# Tiefenentladeschutz_2.net
KiCad netlist of a schematic drawn in EAGLE
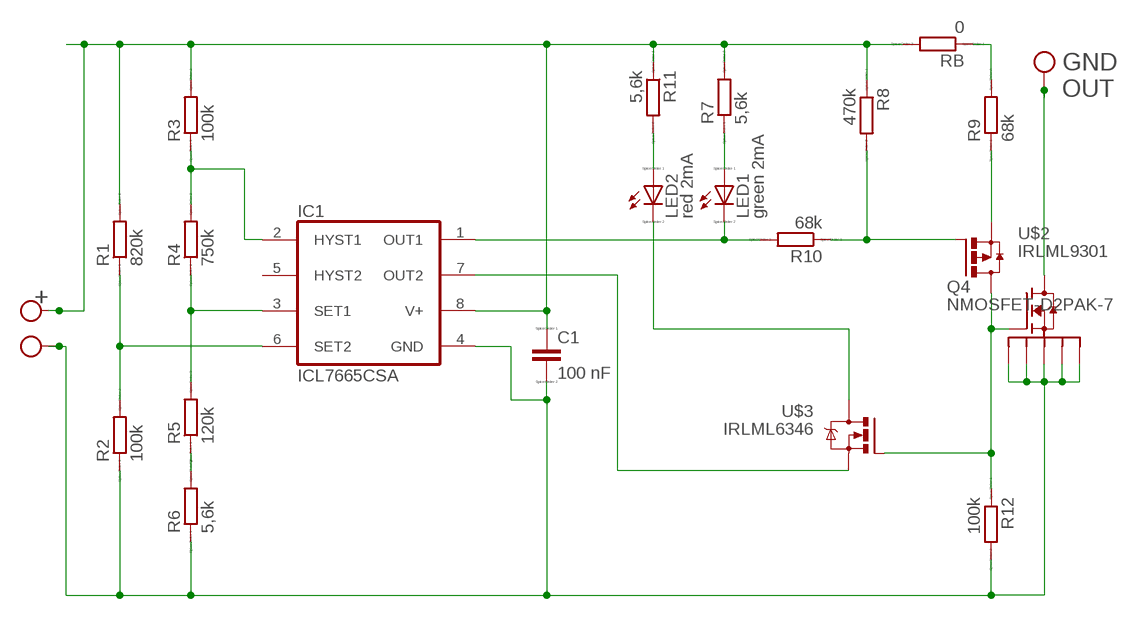
[diagram p0: schematic, sheet 1]

(export (version "E")
  (design (tool "Eeschema 10.0.6"))
  (components
    (comp (ref "C1")
      (value "100 nF")
      (footprint "eagle-import:C1206")
      (libsource (lib "eagle-import") (part "CC1206"))
    )
    (comp (ref "IC1")
      (value "ICL7665CSA")
      (footprint "eagle-import:SO08")
      (fields (field (name "MPN") "ICL7665CSA+"))
      (libsource (lib "eagle-import") (part "ICL7665CSA"))
    )
    (comp (ref "LED1")
      (value "green 2mA")
      (footprint "eagle-import:LED_SML0603")
      (libsource (lib "eagle-import") (part "LED_ESML0603"))
    )
    (comp (ref "LED2")
      (value "red 2mA")
      (footprint "eagle-import:LED_SML0603")
      (libsource (lib "eagle-import") (part "LED_ESML0603"))
    )
    (comp (ref "Q4")
      (value "NMOSFET-D2PAK-7")
      (footprint "eagle-import:H2PAK-6")
      (libsource (lib "eagle-import") (part "NMOSFET-D2PAK-7"))
    )
    (comp (ref "R1")
      (value "820k")
      (footprint "eagle-import:R1206")
      (libsource (lib "eagle-import") (part "RR1206"))
    )
    (comp (ref "R2")
      (value "100k")
      (footprint "eagle-import:R1206")
      (libsource (lib "eagle-import") (part "RR1206"))
    )
    (comp (ref "R3")
      (value "100k")
      (footprint "eagle-import:R1206")
      (libsource (lib "eagle-import") (part "RR1206"))
    )
    (comp (ref "R4")
      (value "750k")
      (footprint "eagle-import:R1206")
      (libsource (lib "eagle-import") (part "RR1206"))
    )
    (comp (ref "R5")
      (value "120k")
      (footprint "eagle-import:R1206")
      (libsource (lib "eagle-import") (part "RR1206"))
    )
    (comp (ref "R6")
      (value "5,6k")
      (footprint "eagle-import:R1206")
      (libsource (lib "eagle-import") (part "RR1206"))
    )
    (comp (ref "R7")
      (value "5,6k")
      (footprint "eagle-import:R1206")
      (libsource (lib "eagle-import") (part "RR1206"))
    )
    (comp (ref "R8")
      (value "470k")
      (footprint "eagle-import:R1206")
      (libsource (lib "eagle-import") (part "RR1206"))
    )
    (comp (ref "R9")
      (value "68k")
      (footprint "eagle-import:R1206")
      (libsource (lib "eagle-import") (part "RR1206"))
    )
    (comp (ref "R10")
      (value "68k")
      (footprint "eagle-import:R1206")
      (libsource (lib "eagle-import") (part "RR1206"))
    )
    (comp (ref "R11")
      (value "5,6k")
      (footprint "eagle-import:R1206")
      (libsource (lib "eagle-import") (part "RR1206"))
    )
    (comp (ref "R12")
      (value "100k")
      (footprint "eagle-import:R1206")
      (libsource (lib "eagle-import") (part "RR1206"))
    )
    (comp (ref "RB")
      (value "0")
      (footprint "eagle-import:R1206")
      (libsource (lib "eagle-import") (part "RR1206"))
    )
    (comp (ref "U$2")
      (value "IRLML9301")
      (footprint "eagle-import:SOT-23")
      (libsource (lib "eagle-import") (part "IRLML9301"))
    )
    (comp (ref "U$3")
      (value "IRLML6346")
      (footprint "eagle-import:SOT-23")
      (libsource (lib "eagle-import") (part "IRLML6346"))
    )
    (comp (ref "U$4")
      (value "PINBIG")
      (footprint "eagle-import:PIN")
      (libsource (lib "eagle-import") (part "PINBIG"))
    )
    (comp (ref "U$6")
      (value "PIN1.27")
      (footprint "eagle-import:PIN-1.27")
      (libsource (lib "eagle-import") (part "PIN1.27"))
    )
    (comp (ref "U$7")
      (value "PIN1.27")
      (footprint "eagle-import:PIN-1.27")
      (libsource (lib "eagle-import") (part "PIN1.27"))
    )
  )
  (nets
    (net (code "1") (name "Net-(IC1-GND)") (class "Default")
      (node (ref "C1") (pin "2") (pinfunction "2_2") (pintype "passive"))
      (node (ref "IC1") (pin "4") (pinfunction "GND_4") (pintype "power_in"))
      (node (ref "Q4") (pin "S1") (pinfunction "S1_S1") (pintype "passive"))
      (node (ref "Q4") (pin "S2") (pinfunction "S2_S2") (pintype "passive"))
      (node (ref "Q4") (pin "S3") (pinfunction "S3_S3") (pintype "passive"))
      (node (ref "Q4") (pin "S4") (pinfunction "S4_S4") (pintype "passive"))
      (node (ref "Q4") (pin "S5") (pinfunction "S5_S5") (pintype "passive"))
      (node (ref "R12") (pin "2") (pinfunction "2_2") (pintype "passive"))
      (node (ref "R2") (pin "1") (pinfunction "1_1") (pintype "passive"))
      (node (ref "R6") (pin "1") (pinfunction "1_1") (pintype "passive"))
      (node (ref "U$6") (pin "P$1") (pinfunction "P$1_P$1") (pintype "bidirectional"))
    )
    (net (code "2") (name "Net-(IC1-HYST1)") (class "Default")
      (node (ref "IC1") (pin "2") (pinfunction "HYST1_2") (pintype "input"))
      (node (ref "R3") (pin "1") (pinfunction "1_1") (pintype "passive"))
      (node (ref "R4") (pin "2") (pinfunction "2_2") (pintype "passive"))
    )
    (net (code "3") (name "Net-(IC1-OUT1)") (class "Default")
      (node (ref "IC1") (pin "1") (pinfunction "OUT1_1") (pintype "output"))
      (node (ref "LED1") (pin "C") (pinfunction "C_C") (pintype "passive"))
      (node (ref "R10") (pin "2") (pinfunction "2_2") (pintype "passive"))
    )
    (net (code "4") (name "Net-(IC1-OUT2)") (class "Default")
      (node (ref "IC1") (pin "7") (pinfunction "OUT2_7") (pintype "output"))
      (node (ref "U$3") (pin "2") (pinfunction "S_2") (pintype "passive"))
    )
    (net (code "5") (name "Net-(IC1-SET1)") (class "Default")
      (node (ref "IC1") (pin "3") (pinfunction "SET1_3") (pintype "input"))
      (node (ref "R4") (pin "1") (pinfunction "1_1") (pintype "passive"))
      (node (ref "R5") (pin "2") (pinfunction "2_2") (pintype "passive"))
    )
    (net (code "6") (name "Net-(IC1-SET2)") (class "Default")
      (node (ref "IC1") (pin "6") (pinfunction "SET2_6") (pintype "input"))
      (node (ref "R1") (pin "1") (pinfunction "1_1") (pintype "passive"))
      (node (ref "R2") (pin "2") (pinfunction "2_2") (pintype "passive"))
    )
    (net (code "7") (name "Net-(IC1-V+)") (class "Default")
      (node (ref "C1") (pin "1") (pinfunction "1_1") (pintype "passive"))
      (node (ref "IC1") (pin "8") (pinfunction "V+_8") (pintype "power_in"))
      (node (ref "R1") (pin "2") (pinfunction "2_2") (pintype "passive"))
      (node (ref "R11") (pin "1") (pinfunction "1_1") (pintype "passive"))
      (node (ref "R3") (pin "2") (pinfunction "2_2") (pintype "passive"))
      (node (ref "R7") (pin "2") (pinfunction "2_2") (pintype "passive"))
      (node (ref "R8") (pin "1") (pinfunction "1_1") (pintype "passive"))
      (node (ref "RB") (pin "2") (pinfunction "2_2") (pintype "passive"))
      (node (ref "U$4") (pin "P$1") (pinfunction "P$1_P$1") (pintype "bidirectional"))
    )
    (net (code "8") (name "Net-(LED1-PadA)") (class "Default")
      (node (ref "LED1") (pin "A") (pinfunction "A_A") (pintype "passive"))
      (node (ref "R7") (pin "1") (pinfunction "1_1") (pintype "passive"))
    )
    (net (code "9") (name "Net-(LED2-PadA)") (class "Default")
      (node (ref "LED2") (pin "A") (pinfunction "A_A") (pintype "passive"))
      (node (ref "R11") (pin "2") (pinfunction "2_2") (pintype "passive"))
    )
    (net (code "10") (name "Net-(Q4-PadD)") (class "Default")
      (node (ref "Q4") (pin "D") (pinfunction "D_D") (pintype "passive"))
      (node (ref "U$7") (pin "P$1") (pinfunction "P$1_P$1") (pintype "bidirectional"))
    )
    (net (code "11") (name "Net-(R5-Pad1)") (class "Default")
      (node (ref "R5") (pin "1") (pinfunction "1_1") (pintype "passive"))
      (node (ref "R6") (pin "2") (pinfunction "2_2") (pintype "passive"))
    )
    (net (code "12") (name "Net-(R9-Pad2)") (class "Default")
      (node (ref "R9") (pin "2") (pinfunction "2_2") (pintype "passive"))
      (node (ref "RB") (pin "1") (pinfunction "1_1") (pintype "passive"))
    )
    (net (code "13") (name "Net-(U$2-D)") (class "Default")
      (node (ref "Q4") (pin "G") (pinfunction "G_G") (pintype "passive"))
      (node (ref "R12") (pin "1") (pinfunction "1_1") (pintype "passive"))
      (node (ref "U$2") (pin "1") (pinfunction "D_1") (pintype "passive"))
      (node (ref "U$3") (pin "3") (pinfunction "G_3") (pintype "passive"))
    )
    (net (code "14") (name "Net-(U$2-G)") (class "Default")
      (node (ref "R10") (pin "1") (pinfunction "1_1") (pintype "passive"))
      (node (ref "R8") (pin "2") (pinfunction "2_2") (pintype "passive"))
      (node (ref "U$2") (pin "3") (pinfunction "G_3") (pintype "passive"))
    )
    (net (code "15") (name "Net-(U$2-S)") (class "Default")
      (node (ref "R9") (pin "1") (pinfunction "1_1") (pintype "passive"))
      (node (ref "U$2") (pin "2") (pinfunction "S_2") (pintype "passive"))
    )
    (net (code "16") (name "Net-(U$3-D)") (class "Default")
      (node (ref "LED2") (pin "C") (pinfunction "C_C") (pintype "passive"))
      (node (ref "U$3") (pin "1") (pinfunction "D_1") (pintype "passive"))
    )
    (net (code "17") (name "unconnected-(IC1-HYST2-Pad5)") (class "Default")
      (node (ref "IC1") (pin "5") (pinfunction "HYST2_5") (pintype "input"))
    )
  )
)
